# pycopter_board_v1.net
KiCad netlist of a schematic drawn in EAGLE
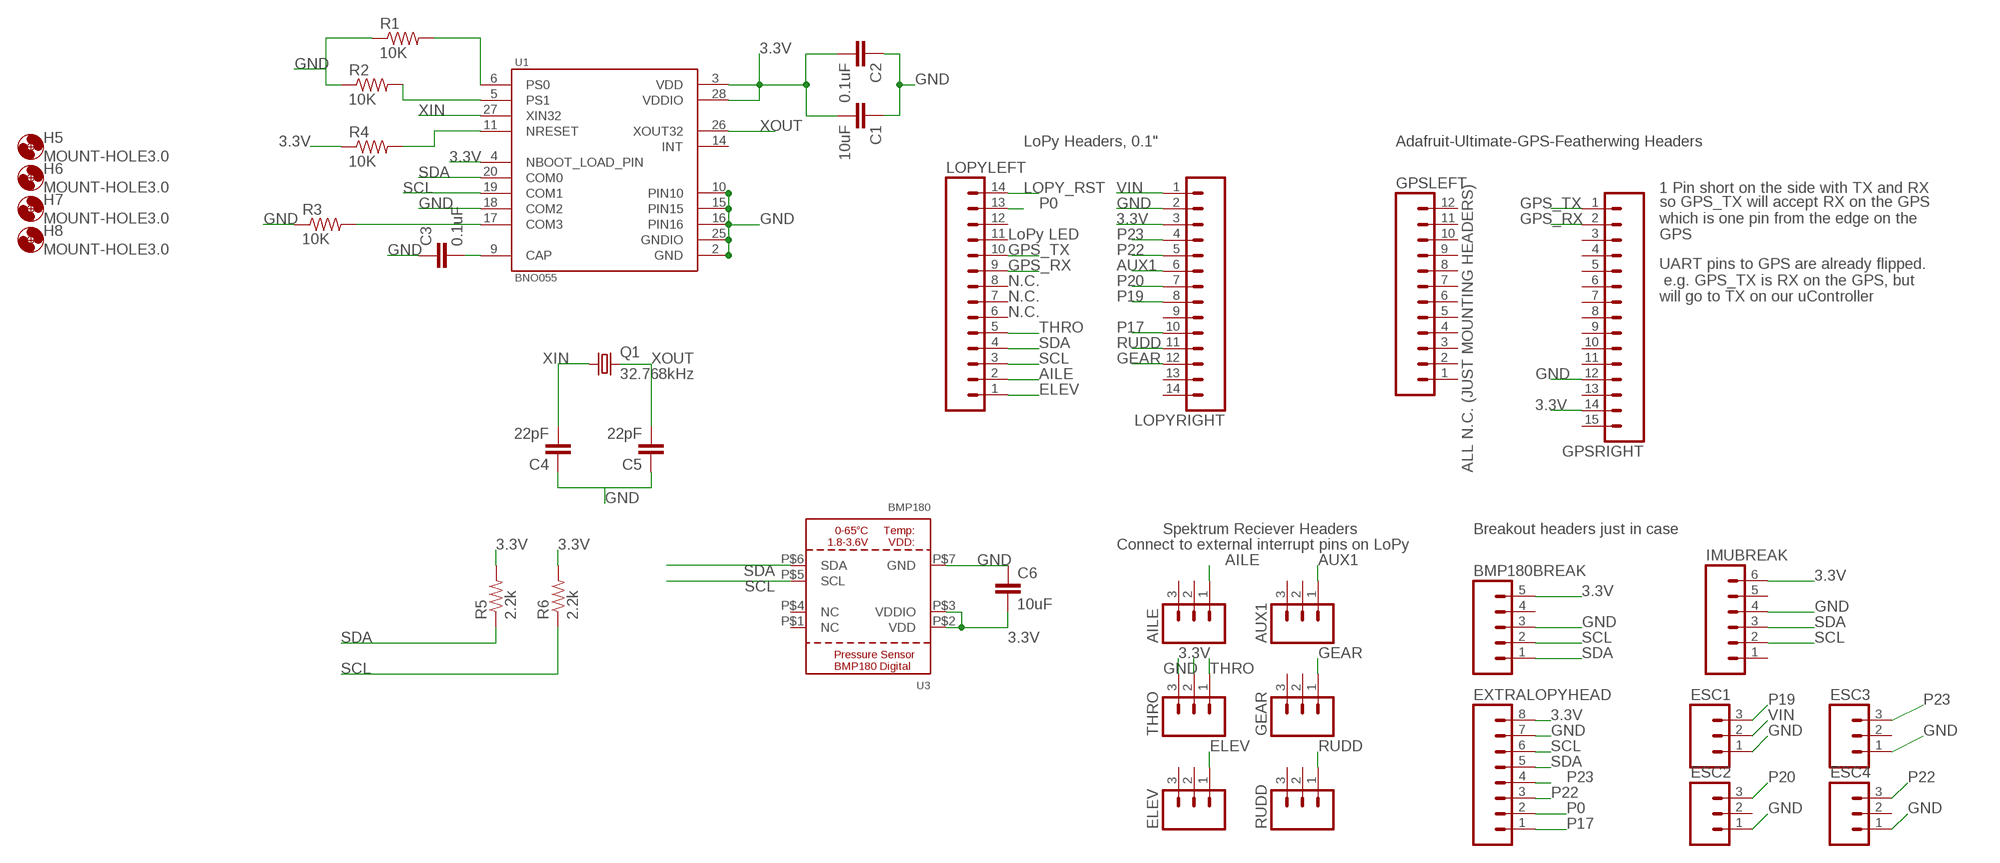
[diagram p0: schematic, sheet 1]

(export (version "E")
  (design (tool "Eeschema 10.0.6"))
  (components
    (comp (ref "AILE")
      (value "M03PTH")
      (footprint "eagle-import:1X03")
      (libsource (lib "eagle-import") (part "M03PTH"))
    )
    (comp (ref "AUX1")
      (value "M03PTH")
      (footprint "eagle-import:1X03")
      (libsource (lib "eagle-import") (part "M03PTH"))
    )
    (comp (ref "BMP180BREAK")
      (value "M05PTH")
      (footprint "eagle-import:1X05")
      (libsource (lib "eagle-import") (part "M05PTH"))
    )
    (comp (ref "C1")
      (value "10uF")
      (footprint "eagle-import:0402-CAP")
      (libsource (lib "eagle-import") (part "CAP0402-CAP"))
    )
    (comp (ref "C2")
      (value "0.1uF")
      (footprint "eagle-import:0402-CAP")
      (libsource (lib "eagle-import") (part "CAP0402-CAP"))
    )
    (comp (ref "C3")
      (value "0.1uF")
      (footprint "eagle-import:0402-CAP")
      (libsource (lib "eagle-import") (part "CAP0402-CAP"))
    )
    (comp (ref "C4")
      (value "22pF")
      (footprint "eagle-import:0402-CAP")
      (libsource (lib "eagle-import") (part "CAP0402-CAP"))
    )
    (comp (ref "C5")
      (value "22pF")
      (footprint "eagle-import:0402-CAP")
      (libsource (lib "eagle-import") (part "CAP0402-CAP"))
    )
    (comp (ref "C6")
      (value "10uF")
      (footprint "eagle-import:0402-CAP")
      (libsource (lib "eagle-import") (part "CAP0402-CAP"))
    )
    (comp (ref "ELEV")
      (value "M03PTH")
      (footprint "eagle-import:1X03")
      (libsource (lib "eagle-import") (part "M03PTH"))
    )
    (comp (ref "ESC1")
      (value "M03PTH")
      (footprint "eagle-import:1X03")
      (libsource (lib "eagle-import") (part "M03PTH"))
    )
    (comp (ref "ESC2")
      (value "M03PTH")
      (footprint "eagle-import:1X03")
      (libsource (lib "eagle-import") (part "M03PTH"))
    )
    (comp (ref "ESC3")
      (value "M03PTH")
      (footprint "eagle-import:1X03")
      (libsource (lib "eagle-import") (part "M03PTH"))
    )
    (comp (ref "ESC4")
      (value "M03PTH")
      (footprint "eagle-import:1X03")
      (libsource (lib "eagle-import") (part "M03PTH"))
    )
    (comp (ref "EXTRALOPYHEAD")
      (value "M08SILK_FEMALE_PTH")
      (footprint "eagle-import:1X08")
      (libsource (lib "eagle-import") (part "M08SILK_FEMALE_PTH"))
    )
    (comp (ref "GEAR")
      (value "M03PTH")
      (footprint "eagle-import:1X03")
      (libsource (lib "eagle-import") (part "M03PTH"))
    )
    (comp (ref "GPSLEFT")
      (value "M12PTH")
      (footprint "eagle-import:1X12")
      (libsource (lib "eagle-import") (part "M12PTH"))
    )
    (comp (ref "GPSRIGHT")
      (value "M15")
      (footprint "eagle-import:1X15")
      (libsource (lib "eagle-import") (part "M15"))
    )
    (comp (ref "H5")
      (value "MOUNT-HOLE3.0")
      (footprint "eagle-import:3,0")
      (libsource (lib "eagle-import") (part "MOUNT-HOLE3.0"))
    )
    (comp (ref "H6")
      (value "MOUNT-HOLE3.0")
      (footprint "eagle-import:3,0")
      (libsource (lib "eagle-import") (part "MOUNT-HOLE3.0"))
    )
    (comp (ref "H7")
      (value "MOUNT-HOLE3.0")
      (footprint "eagle-import:3,0")
      (libsource (lib "eagle-import") (part "MOUNT-HOLE3.0"))
    )
    (comp (ref "H8")
      (value "MOUNT-HOLE3.0")
      (footprint "eagle-import:3,0")
      (libsource (lib "eagle-import") (part "MOUNT-HOLE3.0"))
    )
    (comp (ref "IMUBREAK")
      (value "M06SILK_FEMALE_PTH")
      (footprint "eagle-import:1X06")
      (libsource (lib "eagle-import") (part "M06SILK_FEMALE_PTH"))
    )
    (comp (ref "LOPYLEFT")
      (value "M14")
      (footprint "eagle-import:1X14")
      (libsource (lib "eagle-import") (part "M14"))
    )
    (comp (ref "LOPYRIGHT")
      (value "M14")
      (footprint "eagle-import:1X14")
      (libsource (lib "eagle-import") (part "M14"))
    )
    (comp (ref "Q1")
      (value "32.768kHz")
      (footprint "eagle-import:TC38H")
      (libsource (lib "eagle-import") (part "CRYSTALTC38H"))
    )
    (comp (ref "R1")
      (value "10K")
      (footprint "eagle-import:0402-RES")
      (libsource (lib "eagle-import") (part "RESISTOR0402-RES"))
    )
    (comp (ref "R2")
      (value "10K")
      (footprint "eagle-import:0402-RES")
      (libsource (lib "eagle-import") (part "RESISTOR0402-RES"))
    )
    (comp (ref "R3")
      (value "10K")
      (footprint "eagle-import:0402-RES")
      (libsource (lib "eagle-import") (part "RESISTOR0402-RES"))
    )
    (comp (ref "R4")
      (value "10K")
      (footprint "eagle-import:0402-RES")
      (libsource (lib "eagle-import") (part "RESISTOR0402-RES"))
    )
    (comp (ref "R5")
      (value "2.2k")
      (footprint "eagle-import:0402-RES")
      (libsource (lib "eagle-import") (part "RESISTOR0402-RES"))
    )
    (comp (ref "R6")
      (value "2.2k")
      (footprint "eagle-import:0402-RES")
      (libsource (lib "eagle-import") (part "RESISTOR0402-RES"))
    )
    (comp (ref "RUDD")
      (value "M03PTH")
      (footprint "eagle-import:1X03")
      (libsource (lib "eagle-import") (part "M03PTH"))
    )
    (comp (ref "THRO")
      (value "M03PTH")
      (footprint "eagle-import:1X03")
      (libsource (lib "eagle-import") (part "M03PTH"))
    )
    (comp (ref "U1")
      (value "BNO055")
      (footprint "eagle-import:LGA28R50P4X10_380X520X100")
      (fields (field (name "MF") "Bosch"))
      (libsource (lib "eagle-import") (part "BNO055"))
    )
    (comp (ref "U3")
      (value "BMP180")
      (footprint "eagle-import:BMP180_EXTENDED")
      (libsource (lib "eagle-import") (part "BMP180EXT"))
    )
  )
  (nets
    (net (code "1") (name "/3.3V") (class "Default")
      (node (ref "BMP180BREAK") (pin "5") (pinfunction "5_5") (pintype "passive"))
      (node (ref "C1") (pin "2") (pinfunction "2_2") (pintype "passive"))
      (node (ref "C2") (pin "2") (pinfunction "2_2") (pintype "passive"))
      (node (ref "C6") (pin "2") (pinfunction "2_2") (pintype "passive"))
      (node (ref "EXTRALOPYHEAD") (pin "8") (pinfunction "8_8") (pintype "passive"))
      (node (ref "GPSRIGHT") (pin "14") (pinfunction "14_14") (pintype "passive"))
      (node (ref "IMUBREAK") (pin "6") (pinfunction "6_6") (pintype "passive"))
      (node (ref "LOPYRIGHT") (pin "3") (pinfunction "3_3") (pintype "passive"))
      (node (ref "R4") (pin "1") (pinfunction "1_1") (pintype "passive"))
      (node (ref "R5") (pin "2") (pinfunction "2_2") (pintype "passive"))
      (node (ref "R6") (pin "2") (pinfunction "2_2") (pintype "passive"))
      (node (ref "THRO") (pin "2") (pinfunction "2_2") (pintype "passive"))
      (node (ref "U1") (pin "28") (pinfunction "VDDIO_28") (pintype "power_in"))
      (node (ref "U1") (pin "3") (pinfunction "VDD_3") (pintype "power_in"))
      (node (ref "U1") (pin "4") (pinfunction "NBOOT_LOAD_PIN_4") (pintype "bidirectional"))
      (node (ref "U3") (pin "P$2") (pinfunction "VDD_P$2") (pintype "power_in"))
      (node (ref "U3") (pin "P$3") (pinfunction "VDDIO_P$3") (pintype "power_in"))
    )
    (net (code "2") (name "/AILE") (class "Default")
      (node (ref "AILE") (pin "1") (pinfunction "1_1") (pintype "passive"))
      (node (ref "LOPYLEFT") (pin "2") (pinfunction "2_2") (pintype "passive"))
    )
    (net (code "3") (name "/AUX1") (class "Default")
      (node (ref "AUX1") (pin "1") (pinfunction "1_1") (pintype "passive"))
      (node (ref "LOPYRIGHT") (pin "6") (pinfunction "6_6") (pintype "passive"))
    )
    (net (code "4") (name "/ELEV") (class "Default")
      (node (ref "ELEV") (pin "1") (pinfunction "1_1") (pintype "passive"))
      (node (ref "LOPYLEFT") (pin "1") (pinfunction "1_1") (pintype "passive"))
    )
    (net (code "5") (name "/GEAR") (class "Default")
      (node (ref "GEAR") (pin "1") (pinfunction "1_1") (pintype "passive"))
      (node (ref "LOPYRIGHT") (pin "12") (pinfunction "12_12") (pintype "passive"))
    )
    (net (code "6") (name "/GND") (class "Default")
      (node (ref "BMP180BREAK") (pin "3") (pinfunction "3_3") (pintype "passive"))
      (node (ref "C1") (pin "1") (pinfunction "1_1") (pintype "passive"))
      (node (ref "C2") (pin "1") (pinfunction "1_1") (pintype "passive"))
      (node (ref "C3") (pin "1") (pinfunction "1_1") (pintype "passive"))
      (node (ref "C4") (pin "1") (pinfunction "1_1") (pintype "passive"))
      (node (ref "C5") (pin "1") (pinfunction "1_1") (pintype "passive"))
      (node (ref "C6") (pin "1") (pinfunction "1_1") (pintype "passive"))
      (node (ref "ESC1") (pin "1") (pinfunction "1_1") (pintype "passive"))
      (node (ref "ESC2") (pin "1") (pinfunction "1_1") (pintype "passive"))
      (node (ref "ESC3") (pin "1") (pinfunction "1_1") (pintype "passive"))
      (node (ref "ESC4") (pin "1") (pinfunction "1_1") (pintype "passive"))
      (node (ref "EXTRALOPYHEAD") (pin "7") (pinfunction "7_7") (pintype "passive"))
      (node (ref "GPSRIGHT") (pin "12") (pinfunction "12_12") (pintype "passive"))
      (node (ref "IMUBREAK") (pin "4") (pinfunction "4_4") (pintype "passive"))
      (node (ref "LOPYRIGHT") (pin "2") (pinfunction "2_2") (pintype "passive"))
      (node (ref "R1") (pin "1") (pinfunction "1_1") (pintype "passive"))
      (node (ref "R2") (pin "1") (pinfunction "1_1") (pintype "passive"))
      (node (ref "R3") (pin "1") (pinfunction "1_1") (pintype "passive"))
      (node (ref "THRO") (pin "3") (pinfunction "3_3") (pintype "passive"))
      (node (ref "U1") (pin "10") (pinfunction "PIN10_10") (pintype "power_in"))
      (node (ref "U1") (pin "15") (pinfunction "PIN15_15") (pintype "power_in"))
      (node (ref "U1") (pin "16") (pinfunction "PIN16_16") (pintype "power_in"))
      (node (ref "U1") (pin "18") (pinfunction "COM2_18") (pintype "bidirectional"))
      (node (ref "U1") (pin "2") (pinfunction "GND_2") (pintype "power_in"))
      (node (ref "U1") (pin "25") (pinfunction "GNDIO_25") (pintype "power_in"))
      (node (ref "U3") (pin "P$7") (pinfunction "GND_P$7") (pintype "power_in"))
    )
    (net (code "7") (name "/GPS_RX") (class "Default")
      (node (ref "GPSRIGHT") (pin "2") (pinfunction "2_2") (pintype "passive"))
      (node (ref "LOPYLEFT") (pin "9") (pinfunction "9_9") (pintype "passive"))
    )
    (net (code "8") (name "/GPS_TX") (class "Default")
      (node (ref "GPSRIGHT") (pin "1") (pinfunction "1_1") (pintype "passive"))
      (node (ref "LOPYLEFT") (pin "10") (pinfunction "10_10") (pintype "passive"))
    )
    (net (code "9") (name "/LOPY_RST") (class "Default")
      (node (ref "LOPYLEFT") (pin "14") (pinfunction "14_14") (pintype "passive"))
    )
    (net (code "10") (name "/P0") (class "Default")
      (node (ref "EXTRALOPYHEAD") (pin "2") (pinfunction "2_2") (pintype "passive"))
      (node (ref "LOPYLEFT") (pin "13") (pinfunction "13_13") (pintype "passive"))
    )
    (net (code "11") (name "/P17") (class "Default")
      (node (ref "EXTRALOPYHEAD") (pin "1") (pinfunction "1_1") (pintype "passive"))
      (node (ref "LOPYRIGHT") (pin "10") (pinfunction "10_10") (pintype "passive"))
    )
    (net (code "12") (name "/P19") (class "Default")
      (node (ref "ESC1") (pin "3") (pinfunction "3_3") (pintype "passive"))
      (node (ref "LOPYRIGHT") (pin "8") (pinfunction "8_8") (pintype "passive"))
    )
    (net (code "13") (name "/P20") (class "Default")
      (node (ref "ESC2") (pin "3") (pinfunction "3_3") (pintype "passive"))
      (node (ref "LOPYRIGHT") (pin "7") (pinfunction "7_7") (pintype "passive"))
    )
    (net (code "14") (name "/P22") (class "Default")
      (node (ref "ESC4") (pin "3") (pinfunction "3_3") (pintype "passive"))
      (node (ref "EXTRALOPYHEAD") (pin "3") (pinfunction "3_3") (pintype "passive"))
      (node (ref "LOPYRIGHT") (pin "5") (pinfunction "5_5") (pintype "passive"))
    )
    (net (code "15") (name "/P23") (class "Default")
      (node (ref "ESC3") (pin "3") (pinfunction "3_3") (pintype "passive"))
      (node (ref "EXTRALOPYHEAD") (pin "4") (pinfunction "4_4") (pintype "passive"))
      (node (ref "LOPYRIGHT") (pin "4") (pinfunction "4_4") (pintype "passive"))
    )
    (net (code "16") (name "/RUDD") (class "Default")
      (node (ref "LOPYRIGHT") (pin "11") (pinfunction "11_11") (pintype "passive"))
      (node (ref "RUDD") (pin "1") (pinfunction "1_1") (pintype "passive"))
    )
    (net (code "17") (name "/SCL") (class "Default")
      (node (ref "BMP180BREAK") (pin "2") (pinfunction "2_2") (pintype "passive"))
      (node (ref "EXTRALOPYHEAD") (pin "6") (pinfunction "6_6") (pintype "passive"))
      (node (ref "IMUBREAK") (pin "2") (pinfunction "2_2") (pintype "passive"))
      (node (ref "LOPYLEFT") (pin "3") (pinfunction "3_3") (pintype "passive"))
      (node (ref "R6") (pin "1") (pinfunction "1_1") (pintype "passive"))
      (node (ref "U1") (pin "19") (pinfunction "COM1_19") (pintype "bidirectional"))
      (node (ref "U3") (pin "P$5") (pinfunction "SCL_P$5") (pintype "bidirectional"))
    )
    (net (code "18") (name "/SDA") (class "Default")
      (node (ref "BMP180BREAK") (pin "1") (pinfunction "1_1") (pintype "passive"))
      (node (ref "EXTRALOPYHEAD") (pin "5") (pinfunction "5_5") (pintype "passive"))
      (node (ref "IMUBREAK") (pin "3") (pinfunction "3_3") (pintype "passive"))
      (node (ref "LOPYLEFT") (pin "4") (pinfunction "4_4") (pintype "passive"))
      (node (ref "R5") (pin "1") (pinfunction "1_1") (pintype "passive"))
      (node (ref "U1") (pin "20") (pinfunction "COM0_20") (pintype "bidirectional"))
      (node (ref "U3") (pin "P$6") (pinfunction "SDA_P$6") (pintype "bidirectional"))
    )
    (net (code "19") (name "/THRO") (class "Default")
      (node (ref "LOPYLEFT") (pin "5") (pinfunction "5_5") (pintype "passive"))
      (node (ref "THRO") (pin "1") (pinfunction "1_1") (pintype "passive"))
    )
    (net (code "20") (name "/VIN") (class "Default")
      (node (ref "ESC1") (pin "2") (pinfunction "2_2") (pintype "passive"))
      (node (ref "LOPYRIGHT") (pin "1") (pinfunction "1_1") (pintype "passive"))
    )
    (net (code "21") (name "/XIN") (class "Default")
      (node (ref "C4") (pin "2") (pinfunction "2_2") (pintype "passive"))
      (node (ref "Q1") (pin "1") (pinfunction "1_1") (pintype "passive"))
      (node (ref "U1") (pin "27") (pinfunction "XIN32_27") (pintype "input"))
    )
    (net (code "22") (name "/XOUT") (class "Default")
      (node (ref "C5") (pin "2") (pinfunction "2_2") (pintype "passive"))
      (node (ref "Q1") (pin "2") (pinfunction "2_2") (pintype "passive"))
      (node (ref "U1") (pin "26") (pinfunction "XOUT32_26") (pintype "output"))
    )
    (net (code "23") (name "Net-(U1-CAP)") (class "Default")
      (node (ref "C3") (pin "2") (pinfunction "2_2") (pintype "passive"))
      (node (ref "U1") (pin "9") (pinfunction "CAP_9") (pintype "passive"))
    )
    (net (code "24") (name "Net-(U1-COM3)") (class "Default")
      (node (ref "R3") (pin "2") (pinfunction "2_2") (pintype "passive"))
      (node (ref "U1") (pin "17") (pinfunction "COM3_17") (pintype "bidirectional"))
    )
    (net (code "25") (name "Net-(U1-NRESET)") (class "Default")
      (node (ref "R4") (pin "2") (pinfunction "2_2") (pintype "passive"))
      (node (ref "U1") (pin "11") (pinfunction "NRESET_11") (pintype "input"))
    )
    (net (code "26") (name "Net-(U1-PS0)") (class "Default")
      (node (ref "R1") (pin "2") (pinfunction "2_2") (pintype "passive"))
      (node (ref "U1") (pin "6") (pinfunction "PS0_6") (pintype "input"))
    )
    (net (code "27") (name "Net-(U1-PS1)") (class "Default")
      (node (ref "R2") (pin "2") (pinfunction "2_2") (pintype "passive"))
      (node (ref "U1") (pin "5") (pinfunction "PS1_5") (pintype "input"))
    )
    (net (code "28") (name "unconnected-(AILE-Pad2)") (class "Default")
      (node (ref "AILE") (pin "2") (pinfunction "2_2") (pintype "passive"))
    )
    (net (code "29") (name "unconnected-(AILE-Pad3)") (class "Default")
      (node (ref "AILE") (pin "3") (pinfunction "3_3") (pintype "passive"))
    )
    (net (code "30") (name "unconnected-(AUX1-Pad2)") (class "Default")
      (node (ref "AUX1") (pin "2") (pinfunction "2_2") (pintype "passive"))
    )
    (net (code "31") (name "unconnected-(AUX1-Pad3)") (class "Default")
      (node (ref "AUX1") (pin "3") (pinfunction "3_3") (pintype "passive"))
    )
    (net (code "32") (name "unconnected-(BMP180BREAK-Pad4)") (class "Default")
      (node (ref "BMP180BREAK") (pin "4") (pinfunction "4_4") (pintype "passive"))
    )
    (net (code "33") (name "unconnected-(ELEV-Pad2)") (class "Default")
      (node (ref "ELEV") (pin "2") (pinfunction "2_2") (pintype "passive"))
    )
    (net (code "34") (name "unconnected-(ELEV-Pad3)") (class "Default")
      (node (ref "ELEV") (pin "3") (pinfunction "3_3") (pintype "passive"))
    )
    (net (code "35") (name "unconnected-(ESC2-Pad2)") (class "Default")
      (node (ref "ESC2") (pin "2") (pinfunction "2_2") (pintype "passive"))
    )
    (net (code "36") (name "unconnected-(ESC3-Pad2)") (class "Default")
      (node (ref "ESC3") (pin "2") (pinfunction "2_2") (pintype "passive"))
    )
    (net (code "37") (name "unconnected-(ESC4-Pad2)") (class "Default")
      (node (ref "ESC4") (pin "2") (pinfunction "2_2") (pintype "passive"))
    )
    (net (code "38") (name "unconnected-(GEAR-Pad2)") (class "Default")
      (node (ref "GEAR") (pin "2") (pinfunction "2_2") (pintype "passive"))
    )
    (net (code "39") (name "unconnected-(GEAR-Pad3)") (class "Default")
      (node (ref "GEAR") (pin "3") (pinfunction "3_3") (pintype "passive"))
    )
    (net (code "40") (name "unconnected-(GPSLEFT-Pad1)") (class "Default")
      (node (ref "GPSLEFT") (pin "1") (pinfunction "1_1") (pintype "passive"))
    )
    (net (code "41") (name "unconnected-(GPSLEFT-Pad2)") (class "Default")
      (node (ref "GPSLEFT") (pin "2") (pinfunction "2_2") (pintype "passive"))
    )
    (net (code "42") (name "unconnected-(GPSLEFT-Pad3)") (class "Default")
      (node (ref "GPSLEFT") (pin "3") (pinfunction "3_3") (pintype "passive"))
    )
    (net (code "43") (name "unconnected-(GPSLEFT-Pad4)") (class "Default")
      (node (ref "GPSLEFT") (pin "4") (pinfunction "4_4") (pintype "passive"))
    )
    (net (code "44") (name "unconnected-(GPSLEFT-Pad5)") (class "Default")
      (node (ref "GPSLEFT") (pin "5") (pinfunction "5_5") (pintype "passive"))
    )
    (net (code "45") (name "unconnected-(GPSLEFT-Pad6)") (class "Default")
      (node (ref "GPSLEFT") (pin "6") (pinfunction "6_6") (pintype "passive"))
    )
    (net (code "46") (name "unconnected-(GPSLEFT-Pad7)") (class "Default")
      (node (ref "GPSLEFT") (pin "7") (pinfunction "7_7") (pintype "passive"))
    )
    (net (code "47") (name "unconnected-(GPSLEFT-Pad8)") (class "Default")
      (node (ref "GPSLEFT") (pin "8") (pinfunction "8_8") (pintype "passive"))
    )
    (net (code "48") (name "unconnected-(GPSLEFT-Pad9)") (class "Default")
      (node (ref "GPSLEFT") (pin "9") (pinfunction "9_9") (pintype "passive"))
    )
    (net (code "49") (name "unconnected-(GPSLEFT-Pad10)") (class "Default")
      (node (ref "GPSLEFT") (pin "10") (pinfunction "10_10") (pintype "passive"))
    )
    (net (code "50") (name "unconnected-(GPSLEFT-Pad11)") (class "Default")
      (node (ref "GPSLEFT") (pin "11") (pinfunction "11_11") (pintype "passive"))
    )
    (net (code "51") (name "unconnected-(GPSLEFT-Pad12)") (class "Default")
      (node (ref "GPSLEFT") (pin "12") (pinfunction "12_12") (pintype "passive"))
    )
    (net (code "52") (name "unconnected-(GPSRIGHT-Pad3)") (class "Default")
      (node (ref "GPSRIGHT") (pin "3") (pinfunction "3_3") (pintype "passive"))
    )
    (net (code "53") (name "unconnected-(GPSRIGHT-Pad4)") (class "Default")
      (node (ref "GPSRIGHT") (pin "4") (pinfunction "4_4") (pintype "passive"))
    )
    (net (code "54") (name "unconnected-(GPSRIGHT-Pad5)") (class "Default")
      (node (ref "GPSRIGHT") (pin "5") (pinfunction "5_5") (pintype "passive"))
    )
    (net (code "55") (name "unconnected-(GPSRIGHT-Pad6)") (class "Default")
      (node (ref "GPSRIGHT") (pin "6") (pinfunction "6_6") (pintype "passive"))
    )
    (net (code "56") (name "unconnected-(GPSRIGHT-Pad7)") (class "Default")
      (node (ref "GPSRIGHT") (pin "7") (pinfunction "7_7") (pintype "passive"))
    )
    (net (code "57") (name "unconnected-(GPSRIGHT-Pad8)") (class "Default")
      (node (ref "GPSRIGHT") (pin "8") (pinfunction "8_8") (pintype "passive"))
    )
    (net (code "58") (name "unconnected-(GPSRIGHT-Pad9)") (class "Default")
      (node (ref "GPSRIGHT") (pin "9") (pinfunction "9_9") (pintype "passive"))
    )
    (net (code "59") (name "unconnected-(GPSRIGHT-Pad10)") (class "Default")
      (node (ref "GPSRIGHT") (pin "10") (pinfunction "10_10") (pintype "passive"))
    )
    (net (code "60") (name "unconnected-(GPSRIGHT-Pad11)") (class "Default")
      (node (ref "GPSRIGHT") (pin "11") (pinfunction "11_11") (pintype "passive"))
    )
    (net (code "61") (name "unconnected-(GPSRIGHT-Pad13)") (class "Default")
      (node (ref "GPSRIGHT") (pin "13") (pinfunction "13_13") (pintype "passive"))
    )
    (net (code "62") (name "unconnected-(GPSRIGHT-Pad15)") (class "Default")
      (node (ref "GPSRIGHT") (pin "15") (pinfunction "15_15") (pintype "passive"))
    )
    (net (code "63") (name "unconnected-(IMUBREAK-Pad1)") (class "Default")
      (node (ref "IMUBREAK") (pin "1") (pinfunction "1_1") (pintype "passive"))
    )
    (net (code "64") (name "unconnected-(IMUBREAK-Pad5)") (class "Default")
      (node (ref "IMUBREAK") (pin "5") (pinfunction "5_5") (pintype "passive"))
    )
    (net (code "65") (name "unconnected-(LOPYLEFT-Pad6)") (class "Default")
      (node (ref "LOPYLEFT") (pin "6") (pinfunction "6_6") (pintype "passive"))
    )
    (net (code "66") (name "unconnected-(LOPYLEFT-Pad7)") (class "Default")
      (node (ref "LOPYLEFT") (pin "7") (pinfunction "7_7") (pintype "passive"))
    )
    (net (code "67") (name "unconnected-(LOPYLEFT-Pad8)") (class "Default")
      (node (ref "LOPYLEFT") (pin "8") (pinfunction "8_8") (pintype "passive"))
    )
    (net (code "68") (name "unconnected-(LOPYLEFT-Pad11)") (class "Default")
      (node (ref "LOPYLEFT") (pin "11") (pinfunction "11_11") (pintype "passive"))
    )
    (net (code "69") (name "unconnected-(LOPYLEFT-Pad12)") (class "Default")
      (node (ref "LOPYLEFT") (pin "12") (pinfunction "12_12") (pintype "passive"))
    )
    (net (code "70") (name "unconnected-(LOPYRIGHT-Pad9)") (class "Default")
      (node (ref "LOPYRIGHT") (pin "9") (pinfunction "9_9") (pintype "passive"))
    )
    (net (code "71") (name "unconnected-(LOPYRIGHT-Pad13)") (class "Default")
      (node (ref "LOPYRIGHT") (pin "13") (pinfunction "13_13") (pintype "passive"))
    )
    (net (code "72") (name "unconnected-(LOPYRIGHT-Pad14)") (class "Default")
      (node (ref "LOPYRIGHT") (pin "14") (pinfunction "14_14") (pintype "passive"))
    )
    (net (code "73") (name "unconnected-(RUDD-Pad2)") (class "Default")
      (node (ref "RUDD") (pin "2") (pinfunction "2_2") (pintype "passive"))
    )
    (net (code "74") (name "unconnected-(RUDD-Pad3)") (class "Default")
      (node (ref "RUDD") (pin "3") (pinfunction "3_3") (pintype "passive"))
    )
    (net (code "75") (name "unconnected-(U1-INT-Pad14)") (class "Default")
      (node (ref "U1") (pin "14") (pinfunction "INT_14") (pintype "output"))
    )
    (net (code "76") (name "unconnected-(U3-NC-PadP$1)") (class "Default")
      (node (ref "U3") (pin "P$1") (pinfunction "NC_P$1") (pintype "no_connect"))
    )
    (net (code "77") (name "unconnected-(U3-NC-PadP$4)") (class "Default")
      (node (ref "U3") (pin "P$4") (pinfunction "NC_P$4") (pintype "no_connect"))
    )
  )
)
